# Adafruit_VCNL4020_Proximity_and_Light_Se.net
KiCad netlist of a schematic drawn in EAGLE
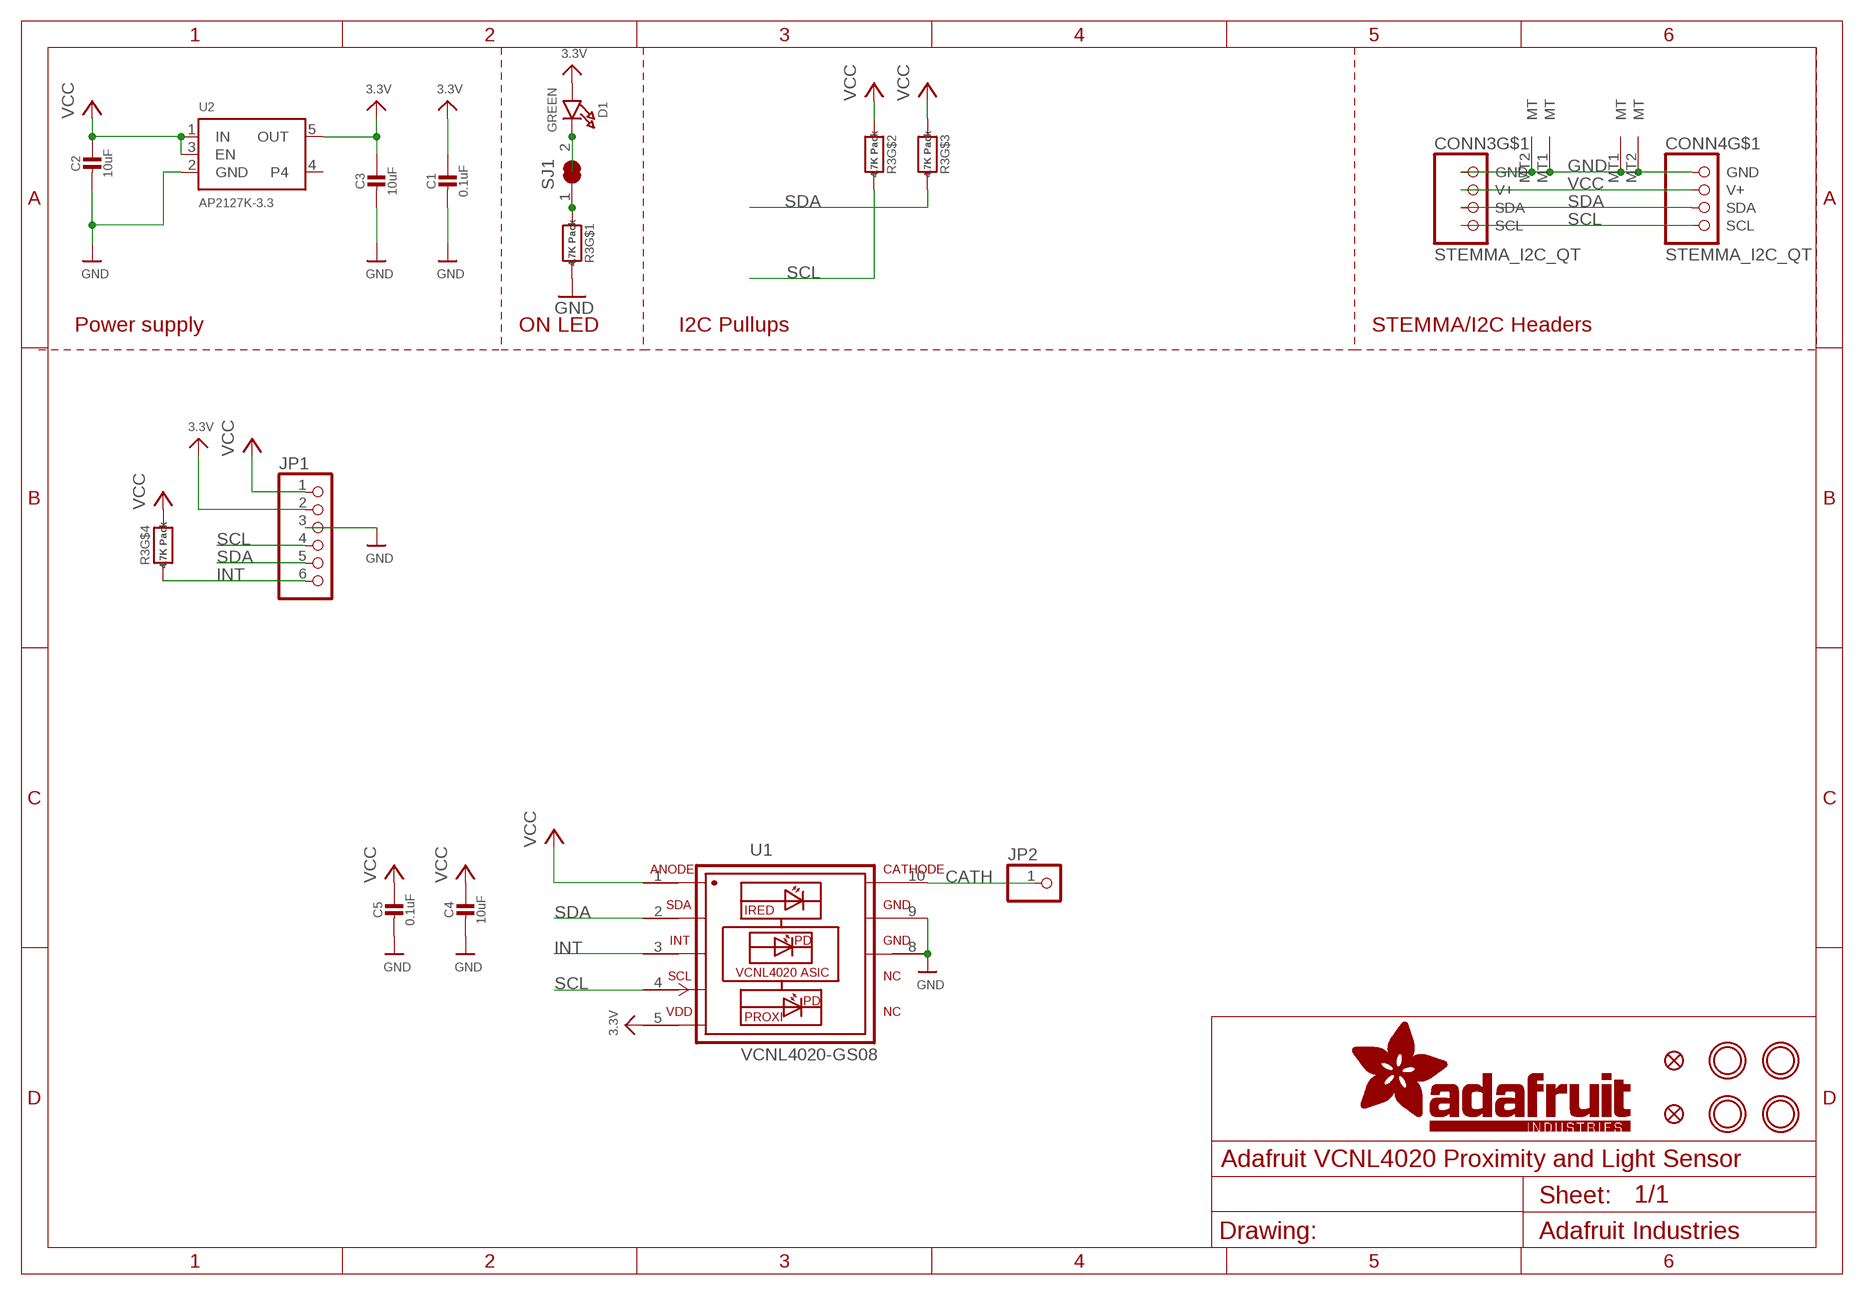
[diagram p0: schematic, sheet 1]

(export (version "E")
  (design (tool "Eeschema 10.0.6"))
  (components
    (comp (ref "C1")
      (value "0.1uF")
      (footprint "eagle-import:0603-NO")
      (libsource (lib "eagle-import") (part "CAP_CERAMIC0603_NO"))
    )
    (comp (ref "C2")
      (value "10uF")
      (footprint "eagle-import:0805-NO")
      (libsource (lib "eagle-import") (part "CAP_CERAMIC0805-NOOUTLINE"))
    )
    (comp (ref "C3")
      (value "10uF")
      (footprint "eagle-import:0805-NO")
      (libsource (lib "eagle-import") (part "CAP_CERAMIC0805-NOOUTLINE"))
    )
    (comp (ref "C4")
      (value "10uF")
      (footprint "eagle-import:0805-NO")
      (libsource (lib "eagle-import") (part "CAP_CERAMIC0805-NOOUTLINE"))
    )
    (comp (ref "C5")
      (value "0.1uF")
      (footprint "eagle-import:0603-NO")
      (libsource (lib "eagle-import") (part "CAP_CERAMIC0603_NO"))
    )
    (comp (ref "CONN3")
      (value "STEMMA_I2C_QT")
      (footprint "eagle-import:JST_SH4")
      (libsource (lib "eagle-import") (part "STEMMA_I2C_QT"))
    )
    (comp (ref "CONN4")
      (value "STEMMA_I2C_QT")
      (footprint "eagle-import:JST_SH4")
      (libsource (lib "eagle-import") (part "STEMMA_I2C_QT"))
    )
    (comp (ref "D1")
      (value "GREEN")
      (footprint "eagle-import:CHIPLED_0603_NOOUTLINE")
      (libsource (lib "eagle-import") (part "LED0603_NOOUTLINE"))
    )
    (comp (ref "FID3")
      (value "FIDUCIAL_1MM")
      (footprint "eagle-import:FIDUCIAL_1MM")
      (libsource (lib "eagle-import") (part "FIDUCIAL_1MM"))
    )
    (comp (ref "FID4")
      (value "FIDUCIAL_1MM")
      (footprint "eagle-import:FIDUCIAL_1MM")
      (libsource (lib "eagle-import") (part "FIDUCIAL_1MM"))
    )
    (comp (ref "JP1")
      (value "HEADER-1X670MIL")
      (footprint "eagle-import:1X06_ROUND_70")
      (libsource (lib "eagle-import") (part "HEADER-1X670MIL"))
    )
    (comp (ref "JP2")
      (value "HEADER-1X1ROUND")
      (footprint "eagle-import:1X01_ROUND")
      (libsource (lib "eagle-import") (part "HEADER-1X1ROUND"))
    )
    (comp (ref "R3")
      (value "4.7K Pack")
      (footprint "eagle-import:RESPACK_4X0603")
      (libsource (lib "eagle-import") (part "RESISTOR_4PACK"))
    )
    (comp (ref "SJ1")
      (value "SOLDERJUMPER_CLOSED")
      (footprint "eagle-import:SOLDERJUMPER_CLOSEDWIRE")
      (libsource (lib "eagle-import") (part "SOLDERJUMPER_CLOSED"))
    )
    (comp (ref "U$1")
      (value "MOUNTINGHOLE2.5")
      (footprint "eagle-import:MOUNTINGHOLE_2.5_PLATED")
      (libsource (lib "eagle-import") (part "MOUNTINGHOLE2.5"))
    )
    (comp (ref "U$17")
      (value "MOUNTINGHOLE2.5")
      (footprint "eagle-import:MOUNTINGHOLE_2.5_PLATED")
      (libsource (lib "eagle-import") (part "MOUNTINGHOLE2.5"))
    )
    (comp (ref "U$19")
      (value "MOUNTINGHOLE2.5")
      (footprint "eagle-import:MOUNTINGHOLE_2.5_PLATED")
      (libsource (lib "eagle-import") (part "MOUNTINGHOLE2.5"))
    )
    (comp (ref "U$21")
      (value "MOUNTINGHOLE2.5")
      (footprint "eagle-import:MOUNTINGHOLE_2.5_PLATED")
      (libsource (lib "eagle-import") (part "MOUNTINGHOLE2.5"))
    )
    (comp (ref "U1")
      (value "VCNL4020-GS08")
      (footprint "eagle-import:PHODET_VCNL4020")
      (fields (field (name "MF") "Vishay Semiconductor"))
      (libsource (lib "eagle-import") (part "VCNL4020-GS08"))
    )
    (comp (ref "U2")
      (value "AP2127K-3.3")
      (footprint "eagle-import:SOT23-5")
      (libsource (lib "eagle-import") (part "VREG_SOT23-5"))
    )
  )
  (nets
    (net (code "1") (name "/CATH") (class "Default")
      (node (ref "JP2") (pin "1") (pinfunction "1_1") (pintype "passive"))
      (node (ref "U1") (pin "10") (pinfunction "IR-CATHODE_10") (pintype "passive"))
    )
    (net (code "2") (name "/INT") (class "Default")
      (node (ref "JP1") (pin "6") (pinfunction "6_6") (pintype "passive"))
      (node (ref "R3") (pin "4") (pinfunction "1_4") (pintype "passive"))
      (node (ref "U1") (pin "3") (pinfunction "INT_3") (pintype "output"))
    )
    (net (code "3") (name "/SCL") (class "Default")
      (node (ref "CONN3") (pin "4") (pinfunction "SCL_4") (pintype "passive"))
      (node (ref "CONN4") (pin "4") (pinfunction "SCL_4") (pintype "passive"))
      (node (ref "JP1") (pin "4") (pinfunction "4_4") (pintype "passive"))
      (node (ref "R3") (pin "7") (pinfunction "2_7") (pintype "passive"))
      (node (ref "U1") (pin "4") (pinfunction "SCL_4") (pintype "input"))
    )
    (net (code "4") (name "/SDA") (class "Default")
      (node (ref "CONN3") (pin "3") (pinfunction "SDA_3") (pintype "passive"))
      (node (ref "CONN4") (pin "3") (pinfunction "SDA_3") (pintype "passive"))
      (node (ref "JP1") (pin "5") (pinfunction "5_5") (pintype "passive"))
      (node (ref "R3") (pin "6") (pinfunction "2_6") (pintype "passive"))
      (node (ref "U1") (pin "2") (pinfunction "SDA_2") (pintype "bidirectional"))
    )
    (net (code "5") (name "3.3V") (class "Default")
      (node (ref "C1") (pin "1") (pinfunction "1_1") (pintype "passive"))
      (node (ref "C3") (pin "1") (pinfunction "1_1") (pintype "passive"))
      (node (ref "D1") (pin "A") (pinfunction "A_A") (pintype "passive"))
      (node (ref "JP1") (pin "2") (pinfunction "2_2") (pintype "passive"))
      (node (ref "U1") (pin "5") (pinfunction "VDD_5") (pintype "power_in"))
      (node (ref "U2") (pin "5") (pinfunction "OUT_5") (pintype "power_in"))
    )
    (net (code "6") (name "GND") (class "Default")
      (node (ref "C1") (pin "2") (pinfunction "2_2") (pintype "passive"))
      (node (ref "C2") (pin "2") (pinfunction "2_2") (pintype "passive"))
      (node (ref "C3") (pin "2") (pinfunction "2_2") (pintype "passive"))
      (node (ref "C4") (pin "2") (pinfunction "2_2") (pintype "passive"))
      (node (ref "C5") (pin "2") (pinfunction "2_2") (pintype "passive"))
      (node (ref "CONN3") (pin "1") (pinfunction "GND_1") (pintype "passive"))
      (node (ref "CONN3") (pin "MT1") (pinfunction "MT_MT1") (pintype "bidirectional"))
      (node (ref "CONN3") (pin "MT2") (pinfunction "MT_MT2") (pintype "bidirectional"))
      (node (ref "CONN4") (pin "1") (pinfunction "GND_1") (pintype "passive"))
      (node (ref "CONN4") (pin "MT1") (pinfunction "MT_MT1") (pintype "bidirectional"))
      (node (ref "CONN4") (pin "MT2") (pinfunction "MT_MT2") (pintype "bidirectional"))
      (node (ref "JP1") (pin "3") (pinfunction "3_3") (pintype "passive"))
      (node (ref "R3") (pin "8") (pinfunction "2_8") (pintype "passive"))
      (node (ref "U1") (pin "8") (pinfunction "GND2_8") (pintype "power_in"))
      (node (ref "U1") (pin "9") (pinfunction "GND_9") (pintype "power_in"))
      (node (ref "U2") (pin "2") (pinfunction "GND_2") (pintype "power_in"))
    )
    (net (code "7") (name "Net-(D1-PadC)") (class "Default")
      (node (ref "D1") (pin "C") (pinfunction "C_C") (pintype "passive"))
      (node (ref "SJ1") (pin "2") (pinfunction "2_2") (pintype "passive"))
    )
    (net (code "8") (name "Net-(R3-Pad1)") (class "Default")
      (node (ref "R3") (pin "1") (pinfunction "1_1") (pintype "passive"))
      (node (ref "SJ1") (pin "1") (pinfunction "1_1") (pintype "passive"))
    )
    (net (code "9") (name "VCC") (class "Default")
      (node (ref "C2") (pin "1") (pinfunction "1_1") (pintype "passive"))
      (node (ref "C4") (pin "1") (pinfunction "1_1") (pintype "passive"))
      (node (ref "C5") (pin "1") (pinfunction "1_1") (pintype "passive"))
      (node (ref "CONN3") (pin "2") (pinfunction "V+_2") (pintype "passive"))
      (node (ref "CONN4") (pin "2") (pinfunction "V+_2") (pintype "passive"))
      (node (ref "JP1") (pin "1") (pinfunction "1_1") (pintype "passive"))
      (node (ref "R3") (pin "2") (pinfunction "1_2") (pintype "passive"))
      (node (ref "R3") (pin "3") (pinfunction "1_3") (pintype "passive"))
      (node (ref "R3") (pin "5") (pinfunction "2_5") (pintype "passive"))
      (node (ref "U1") (pin "1") (pinfunction "IR-ANODE_1") (pintype "passive"))
      (node (ref "U2") (pin "1") (pinfunction "IN_1") (pintype "power_in"))
      (node (ref "U2") (pin "3") (pinfunction "EN_3") (pintype "input"))
    )
    (net (code "10") (name "unconnected-(U2-P4-Pad4)") (class "Default")
      (node (ref "U2") (pin "4") (pinfunction "P4_4") (pintype "bidirectional"))
    )
  )
)
